# ZB2.net
KiCad netlist of a schematic drawn in Altium Designer
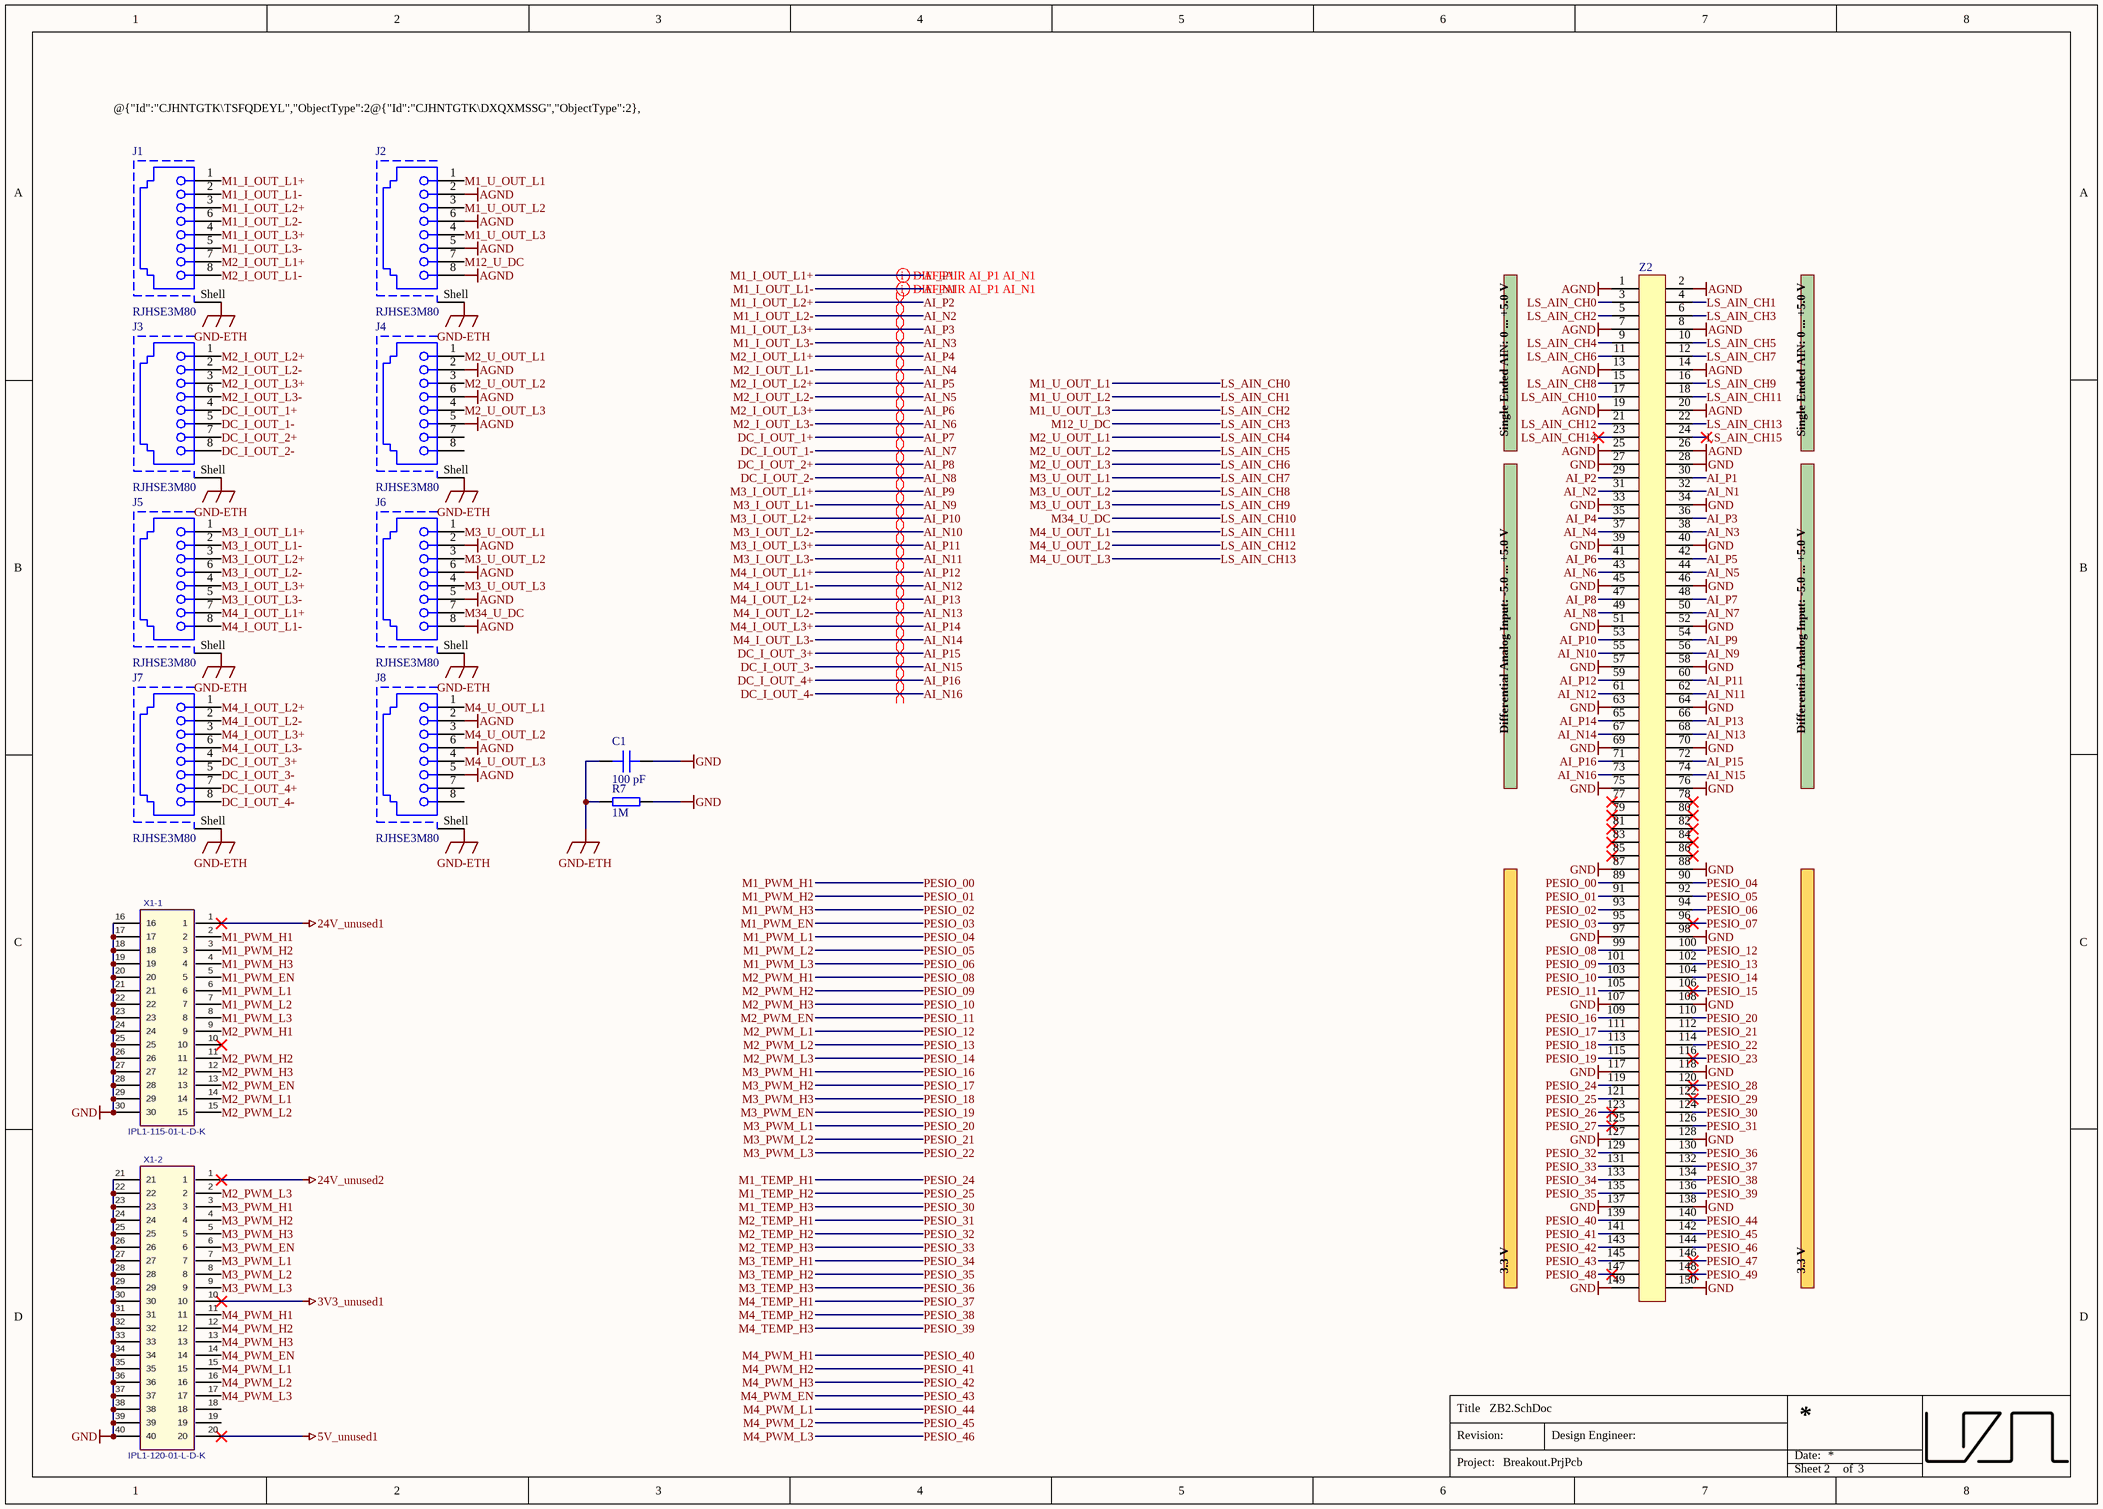
[diagram p0: ZB2.SchDoc]

(export (version "E")
  (design (tool "Eeschema 10.0.6"))
  (components
    (comp (ref "C1")
      (value "100 pF")
      (footprint "C_1206_TE")
      (description "2kV 100pF NP0 ±5% 1206 Multilayer Ceramic Capacitors MLCC - SMD/SMT ROHS")
      (fields
        (field (name "MANUFACTURER PART NUMBER") "CC1206JKNPODBN101")
        (field (name "MANUFACTURER") "YAGEO")
        (field (name "CREATED FROM") "AGeiger")
      )
      (libsource (lib "user") (part "Capacitor"))
    )
    (comp (ref "J1")
      (value "RJHSE3M80")
      (footprint "RJHSE3M80")
      (description "CAT5, RJ45 Connector, 1 port, vertical")
      (fields
        (field (name "MANUFACTURER") "Amphenol")
        (field (name "LCSC PART NUMBER") "C3179193")
        (field (name "CREATED FROM") "DHufnagel")
      )
      (libsource (lib "user") (part "RJHSE3M80"))
    )
    (comp (ref "J2")
      (value "RJHSE3M80")
      (footprint "RJHSE3M80")
      (description "CAT5, RJ45 Connector, 1 port, vertical")
      (fields
        (field (name "MANUFACTURER") "Amphenol")
        (field (name "LCSC PART NUMBER") "C3179193")
        (field (name "CREATED FROM") "DHufnagel")
      )
      (libsource (lib "user") (part "RJHSE3M80"))
    )
    (comp (ref "J3")
      (value "RJHSE3M80")
      (footprint "RJHSE3M80")
      (description "CAT5, RJ45 Connector, 1 port, vertical")
      (fields
        (field (name "MANUFACTURER") "Amphenol")
        (field (name "LCSC PART NUMBER") "C3179193")
        (field (name "CREATED FROM") "DHufnagel")
      )
      (libsource (lib "user") (part "RJHSE3M80"))
    )
    (comp (ref "J4")
      (value "RJHSE3M80")
      (footprint "RJHSE3M80")
      (description "CAT5, RJ45 Connector, 1 port, vertical")
      (fields
        (field (name "MANUFACTURER") "Amphenol")
        (field (name "LCSC PART NUMBER") "C3179193")
        (field (name "CREATED FROM") "DHufnagel")
      )
      (libsource (lib "user") (part "RJHSE3M80"))
    )
    (comp (ref "J5")
      (value "RJHSE3M80")
      (footprint "RJHSE3M80")
      (description "CAT5, RJ45 Connector, 1 port, vertical")
      (fields
        (field (name "MANUFACTURER") "Amphenol")
        (field (name "LCSC PART NUMBER") "C3179193")
        (field (name "CREATED FROM") "DHufnagel")
      )
      (libsource (lib "user") (part "RJHSE3M80"))
    )
    (comp (ref "J6")
      (value "RJHSE3M80")
      (footprint "RJHSE3M80")
      (description "CAT5, RJ45 Connector, 1 port, vertical")
      (fields
        (field (name "MANUFACTURER") "Amphenol")
        (field (name "LCSC PART NUMBER") "C3179193")
        (field (name "CREATED FROM") "DHufnagel")
      )
      (libsource (lib "user") (part "RJHSE3M80"))
    )
    (comp (ref "J7")
      (value "RJHSE3M80")
      (footprint "RJHSE3M80")
      (description "CAT5, RJ45 Connector, 1 port, vertical")
      (fields
        (field (name "MANUFACTURER") "Amphenol")
        (field (name "LCSC PART NUMBER") "C3179193")
        (field (name "CREATED FROM") "DHufnagel")
      )
      (libsource (lib "user") (part "RJHSE3M80"))
    )
    (comp (ref "J8")
      (value "RJHSE3M80")
      (footprint "RJHSE3M80")
      (description "CAT5, RJ45 Connector, 1 port, vertical")
      (fields
        (field (name "MANUFACTURER") "Amphenol")
        (field (name "LCSC PART NUMBER") "C3179193")
        (field (name "CREATED FROM") "DHufnagel")
      )
      (libsource (lib "user") (part "RJHSE3M80"))
    )
    (comp (ref "R7")
      (value "1M")
      (footprint "RES 1206_3216")
      (fields
        (field (name "MANUFACTURER PART NUMBER") "1206W4F1004T5E")
        (field (name "MANUFACTURER") "UNI-ROYAL")
        (field (name "TOLERANCE") "1%")
        (field (name "CREATED FROM") "AGeiger")
      )
      (libsource (lib "user") (part "Resistor"))
    )
    (comp (ref "X1-1")
      (value "IPL1-115-01-L-D-K")
      (footprint "IPL1-115-01-YYY-D-K")
      (description "2.54 mm Double Row Terminal Assembly")
      (fields (field (name "MANUFACTURER") "SAMTEC") (field (name "CREATED FROM") "MGremer"))
      (libsource (lib "user") (part "IPL1-115-01-XX-D-XX"))
    )
    (comp (ref "X1-2")
      (value "IPL1-120-01-L-D-K")
      (footprint "SAMTEC_IPL1-120-01-X-D-K")
      (description "Terminal Assembly, Double Row, Thru-Hole, 2.54 mm x 2.54 mm Pitch, 40 Pins")
      (fields (field (name "MANUFACTURER") "SAMTEC") (field (name "CREATED FROM") "PBaumann"))
      (libsource (lib "user") (part "IPL1-120-01-XX-D-XX"))
    )
    (comp (ref "Z2")
      (value "~")
      (footprint "ERM8-075-02.0-L-DV")
      (description "0.80 mm Edge Rate Rugged High Speed")
      (fields
        (field (name "MANUFACTURER PART NUMBER") "ERM8-075-02.0-L-DV-TR")
        (field (name "MANUFACTURER") "SAMTEC")
        (field (name "CREATED FROM") "AGeiger")
      )
      (libsource (lib "user") (part "CON-150"))
    )
  )
  (nets
    (net (code "1") (name "/AI_N1") (class "Default")
      (node (ref "J1") (pin "2") (pinfunction "2_2") (pintype "passive"))
      (node (ref "Z2") (pin "32") (pinfunction "32_32") (pintype "passive"))
    )
    (net (code "2") (name "/AI_N2") (class "Default")
      (node (ref "J1") (pin "6") (pinfunction "6_6") (pintype "passive"))
      (node (ref "Z2") (pin "31") (pinfunction "31_31") (pintype "passive"))
    )
    (net (code "3") (name "/AI_N3") (class "Default")
      (node (ref "J1") (pin "5") (pinfunction "5_5") (pintype "passive"))
      (node (ref "Z2") (pin "38") (pinfunction "38_38") (pintype "passive"))
    )
    (net (code "4") (name "/AI_N4") (class "Default")
      (node (ref "J1") (pin "8") (pinfunction "8_8") (pintype "passive"))
      (node (ref "Z2") (pin "37") (pinfunction "37_37") (pintype "passive"))
    )
    (net (code "5") (name "/AI_N5") (class "Default")
      (node (ref "J3") (pin "2") (pinfunction "2_2") (pintype "passive"))
      (node (ref "Z2") (pin "44") (pinfunction "44_44") (pintype "passive"))
    )
    (net (code "6") (name "/AI_N6") (class "Default")
      (node (ref "J3") (pin "6") (pinfunction "6_6") (pintype "passive"))
      (node (ref "Z2") (pin "43") (pinfunction "43_43") (pintype "passive"))
    )
    (net (code "7") (name "/AI_N7") (class "Default")
      (node (ref "J3") (pin "5") (pinfunction "5_5") (pintype "passive"))
      (node (ref "Z2") (pin "50") (pinfunction "50_50") (pintype "passive"))
    )
    (net (code "8") (name "/AI_N8") (class "Default")
      (node (ref "J3") (pin "8") (pinfunction "8_8") (pintype "passive"))
      (node (ref "Z2") (pin "49") (pinfunction "49_49") (pintype "passive"))
    )
    (net (code "9") (name "/AI_N9") (class "Default")
      (node (ref "J5") (pin "2") (pinfunction "2_2") (pintype "passive"))
      (node (ref "Z2") (pin "56") (pinfunction "56_56") (pintype "passive"))
    )
    (net (code "10") (name "/AI_N10") (class "Default")
      (node (ref "J5") (pin "6") (pinfunction "6_6") (pintype "passive"))
      (node (ref "Z2") (pin "55") (pinfunction "55_55") (pintype "passive"))
    )
    (net (code "11") (name "/AI_N11") (class "Default")
      (node (ref "J5") (pin "5") (pinfunction "5_5") (pintype "passive"))
      (node (ref "Z2") (pin "62") (pinfunction "62_62") (pintype "passive"))
    )
    (net (code "12") (name "/AI_N12") (class "Default")
      (node (ref "J5") (pin "8") (pinfunction "8_8") (pintype "passive"))
      (node (ref "Z2") (pin "61") (pinfunction "61_61") (pintype "passive"))
    )
    (net (code "13") (name "/AI_N13") (class "Default")
      (node (ref "J7") (pin "2") (pinfunction "2_2") (pintype "passive"))
      (node (ref "Z2") (pin "68") (pinfunction "68_68") (pintype "passive"))
    )
    (net (code "14") (name "/AI_N14") (class "Default")
      (node (ref "J7") (pin "6") (pinfunction "6_6") (pintype "passive"))
      (node (ref "Z2") (pin "67") (pinfunction "67_67") (pintype "passive"))
    )
    (net (code "15") (name "/AI_N15") (class "Default")
      (node (ref "J7") (pin "5") (pinfunction "5_5") (pintype "passive"))
      (node (ref "Z2") (pin "74") (pinfunction "74_74") (pintype "passive"))
    )
    (net (code "16") (name "/AI_N16") (class "Default")
      (node (ref "J7") (pin "8") (pinfunction "8_8") (pintype "passive"))
      (node (ref "Z2") (pin "73") (pinfunction "73_73") (pintype "passive"))
    )
    (net (code "17") (name "/AI_P1") (class "Default")
      (node (ref "J1") (pin "1") (pinfunction "1_1") (pintype "passive"))
      (node (ref "Z2") (pin "30") (pinfunction "30_30") (pintype "passive"))
    )
    (net (code "18") (name "/AI_P2") (class "Default")
      (node (ref "J1") (pin "3") (pinfunction "3_3") (pintype "passive"))
      (node (ref "Z2") (pin "29") (pinfunction "29_29") (pintype "passive"))
    )
    (net (code "19") (name "/AI_P3") (class "Default")
      (node (ref "J1") (pin "4") (pinfunction "4_4") (pintype "passive"))
      (node (ref "Z2") (pin "36") (pinfunction "36_36") (pintype "passive"))
    )
    (net (code "20") (name "/AI_P4") (class "Default")
      (node (ref "J1") (pin "7") (pinfunction "7_7") (pintype "passive"))
      (node (ref "Z2") (pin "35") (pinfunction "35_35") (pintype "passive"))
    )
    (net (code "21") (name "/AI_P5") (class "Default")
      (node (ref "J3") (pin "1") (pinfunction "1_1") (pintype "passive"))
      (node (ref "Z2") (pin "42") (pinfunction "42_42") (pintype "passive"))
    )
    (net (code "22") (name "/AI_P6") (class "Default")
      (node (ref "J3") (pin "3") (pinfunction "3_3") (pintype "passive"))
      (node (ref "Z2") (pin "41") (pinfunction "41_41") (pintype "passive"))
    )
    (net (code "23") (name "/AI_P7") (class "Default")
      (node (ref "J3") (pin "4") (pinfunction "4_4") (pintype "passive"))
      (node (ref "Z2") (pin "48") (pinfunction "48_48") (pintype "passive"))
    )
    (net (code "24") (name "/AI_P8") (class "Default")
      (node (ref "J3") (pin "7") (pinfunction "7_7") (pintype "passive"))
      (node (ref "Z2") (pin "47") (pinfunction "47_47") (pintype "passive"))
    )
    (net (code "25") (name "/AI_P9") (class "Default")
      (node (ref "J5") (pin "1") (pinfunction "1_1") (pintype "passive"))
      (node (ref "Z2") (pin "54") (pinfunction "54_54") (pintype "passive"))
    )
    (net (code "26") (name "/AI_P10") (class "Default")
      (node (ref "J5") (pin "3") (pinfunction "3_3") (pintype "passive"))
      (node (ref "Z2") (pin "53") (pinfunction "53_53") (pintype "passive"))
    )
    (net (code "27") (name "/AI_P11") (class "Default")
      (node (ref "J5") (pin "4") (pinfunction "4_4") (pintype "passive"))
      (node (ref "Z2") (pin "60") (pinfunction "60_60") (pintype "passive"))
    )
    (net (code "28") (name "/AI_P12") (class "Default")
      (node (ref "J5") (pin "7") (pinfunction "7_7") (pintype "passive"))
      (node (ref "Z2") (pin "59") (pinfunction "59_59") (pintype "passive"))
    )
    (net (code "29") (name "/AI_P13") (class "Default")
      (node (ref "J7") (pin "1") (pinfunction "1_1") (pintype "passive"))
      (node (ref "Z2") (pin "66") (pinfunction "66_66") (pintype "passive"))
    )
    (net (code "30") (name "/AI_P14") (class "Default")
      (node (ref "J7") (pin "3") (pinfunction "3_3") (pintype "passive"))
      (node (ref "Z2") (pin "65") (pinfunction "65_65") (pintype "passive"))
    )
    (net (code "31") (name "/AI_P15") (class "Default")
      (node (ref "J7") (pin "4") (pinfunction "4_4") (pintype "passive"))
      (node (ref "Z2") (pin "72") (pinfunction "72_72") (pintype "passive"))
    )
    (net (code "32") (name "/AI_P16") (class "Default")
      (node (ref "J7") (pin "7") (pinfunction "7_7") (pintype "passive"))
      (node (ref "Z2") (pin "71") (pinfunction "71_71") (pintype "passive"))
    )
    (net (code "33") (name "/LS_AIN_CH0") (class "Default")
      (node (ref "J2") (pin "1") (pinfunction "1_1") (pintype "passive"))
      (node (ref "Z2") (pin "3") (pinfunction "3_3") (pintype "passive"))
    )
    (net (code "34") (name "/LS_AIN_CH1") (class "Default")
      (node (ref "J2") (pin "3") (pinfunction "3_3") (pintype "passive"))
      (node (ref "Z2") (pin "4") (pinfunction "4_4") (pintype "passive"))
    )
    (net (code "35") (name "/LS_AIN_CH2") (class "Default")
      (node (ref "J2") (pin "4") (pinfunction "4_4") (pintype "passive"))
      (node (ref "Z2") (pin "5") (pinfunction "5_5") (pintype "passive"))
    )
    (net (code "36") (name "/LS_AIN_CH3") (class "Default")
      (node (ref "J2") (pin "7") (pinfunction "7_7") (pintype "passive"))
      (node (ref "Z2") (pin "6") (pinfunction "6_6") (pintype "passive"))
    )
    (net (code "37") (name "/LS_AIN_CH4") (class "Default")
      (node (ref "J4") (pin "1") (pinfunction "1_1") (pintype "passive"))
      (node (ref "Z2") (pin "9") (pinfunction "9_9") (pintype "passive"))
    )
    (net (code "38") (name "/LS_AIN_CH5") (class "Default")
      (node (ref "J4") (pin "3") (pinfunction "3_3") (pintype "passive"))
      (node (ref "Z2") (pin "10") (pinfunction "10_10") (pintype "passive"))
    )
    (net (code "39") (name "/LS_AIN_CH6") (class "Default")
      (node (ref "J4") (pin "4") (pinfunction "4_4") (pintype "passive"))
      (node (ref "Z2") (pin "11") (pinfunction "11_11") (pintype "passive"))
    )
    (net (code "40") (name "/LS_AIN_CH7") (class "Default")
      (node (ref "J6") (pin "1") (pinfunction "1_1") (pintype "passive"))
      (node (ref "Z2") (pin "12") (pinfunction "12_12") (pintype "passive"))
    )
    (net (code "41") (name "/LS_AIN_CH8") (class "Default")
      (node (ref "J6") (pin "3") (pinfunction "3_3") (pintype "passive"))
      (node (ref "Z2") (pin "15") (pinfunction "15_15") (pintype "passive"))
    )
    (net (code "42") (name "/LS_AIN_CH9") (class "Default")
      (node (ref "J6") (pin "4") (pinfunction "4_4") (pintype "passive"))
      (node (ref "Z2") (pin "16") (pinfunction "16_16") (pintype "passive"))
    )
    (net (code "43") (name "/LS_AIN_CH10") (class "Default")
      (node (ref "J6") (pin "7") (pinfunction "7_7") (pintype "passive"))
      (node (ref "Z2") (pin "17") (pinfunction "17_17") (pintype "passive"))
    )
    (net (code "44") (name "/LS_AIN_CH11") (class "Default")
      (node (ref "J8") (pin "1") (pinfunction "1_1") (pintype "passive"))
      (node (ref "Z2") (pin "18") (pinfunction "18_18") (pintype "passive"))
    )
    (net (code "45") (name "/LS_AIN_CH12") (class "Default")
      (node (ref "J8") (pin "3") (pinfunction "3_3") (pintype "passive"))
      (node (ref "Z2") (pin "21") (pinfunction "21_21") (pintype "passive"))
    )
    (net (code "46") (name "/LS_AIN_CH13") (class "Default")
      (node (ref "J8") (pin "4") (pinfunction "4_4") (pintype "passive"))
      (node (ref "Z2") (pin "22") (pinfunction "22_22") (pintype "passive"))
    )
    (net (code "47") (name "/LS_AIN_CH14") (class "Default")
      (node (ref "Z2") (pin "23") (pinfunction "23_23") (pintype "passive+no_connect"))
    )
    (net (code "48") (name "/LS_AIN_CH15") (class "Default")
      (node (ref "Z2") (pin "24") (pinfunction "24_24") (pintype "passive+no_connect"))
    )
    (net (code "49") (name "/M1_PWM_EN") (class "Default")
      (node (ref "X1-1") (pin "5") (pinfunction "5_5") (pintype "passive"))
      (node (ref "Z2") (pin "95") (pinfunction "95_95") (pintype "passive"))
    )
    (net (code "50") (name "/M1_PWM_H1") (class "Default")
      (node (ref "X1-1") (pin "2") (pinfunction "2_2") (pintype "passive"))
      (node (ref "Z2") (pin "89") (pinfunction "89_89") (pintype "passive"))
    )
    (net (code "51") (name "/M1_PWM_H2") (class "Default")
      (node (ref "X1-1") (pin "3") (pinfunction "3_3") (pintype "passive"))
      (node (ref "Z2") (pin "91") (pinfunction "91_91") (pintype "passive"))
    )
    (net (code "52") (name "/M1_PWM_H3") (class "Default")
      (node (ref "X1-1") (pin "4") (pinfunction "4_4") (pintype "passive"))
      (node (ref "Z2") (pin "93") (pinfunction "93_93") (pintype "passive"))
    )
    (net (code "53") (name "/M1_PWM_L1") (class "Default")
      (node (ref "X1-1") (pin "6") (pinfunction "6_6") (pintype "passive"))
      (node (ref "Z2") (pin "90") (pinfunction "90_90") (pintype "passive"))
    )
    (net (code "54") (name "/M1_PWM_L2") (class "Default")
      (node (ref "X1-1") (pin "7") (pinfunction "7_7") (pintype "passive"))
      (node (ref "Z2") (pin "92") (pinfunction "92_92") (pintype "passive"))
    )
    (net (code "55") (name "/M1_PWM_L3") (class "Default")
      (node (ref "X1-1") (pin "8") (pinfunction "8_8") (pintype "passive"))
      (node (ref "Z2") (pin "94") (pinfunction "94_94") (pintype "passive"))
    )
    (net (code "56") (name "/M1_TEMP_H1") (class "Default")
      (node (ref "Z2") (pin "119") (pinfunction "119_119") (pintype "passive"))
    )
    (net (code "57") (name "/M1_TEMP_H2") (class "Default")
      (node (ref "Z2") (pin "121") (pinfunction "121_121") (pintype "passive"))
    )
    (net (code "58") (name "/M1_TEMP_H3") (class "Default")
      (node (ref "Z2") (pin "124") (pinfunction "124_124") (pintype "passive"))
    )
    (net (code "59") (name "/M2_PWM_EN") (class "Default")
      (node (ref "X1-1") (pin "13") (pinfunction "13_13") (pintype "passive"))
      (node (ref "Z2") (pin "105") (pinfunction "105_105") (pintype "passive"))
    )
    (net (code "60") (name "/M2_PWM_H1") (class "Default")
      (node (ref "X1-1") (pin "9") (pinfunction "9_9") (pintype "passive"))
      (node (ref "Z2") (pin "99") (pinfunction "99_99") (pintype "passive"))
    )
    (net (code "61") (name "/M2_PWM_H2") (class "Default")
      (node (ref "X1-1") (pin "11") (pinfunction "11_11") (pintype "passive"))
      (node (ref "Z2") (pin "101") (pinfunction "101_101") (pintype "passive"))
    )
    (net (code "62") (name "/M2_PWM_H3") (class "Default")
      (node (ref "X1-1") (pin "12") (pinfunction "12_12") (pintype "passive"))
      (node (ref "Z2") (pin "103") (pinfunction "103_103") (pintype "passive"))
    )
    (net (code "63") (name "/M2_PWM_L1") (class "Default")
      (node (ref "X1-1") (pin "14") (pinfunction "14_14") (pintype "passive"))
      (node (ref "Z2") (pin "100") (pinfunction "100_100") (pintype "passive"))
    )
    (net (code "64") (name "/M2_PWM_L2") (class "Default")
      (node (ref "X1-1") (pin "15") (pinfunction "15_15") (pintype "passive"))
      (node (ref "Z2") (pin "102") (pinfunction "102_102") (pintype "passive"))
    )
    (net (code "65") (name "/M2_PWM_L3") (class "Default")
      (node (ref "X1-2") (pin "2") (pinfunction "2_2") (pintype "passive"))
      (node (ref "Z2") (pin "104") (pinfunction "104_104") (pintype "passive"))
    )
    (net (code "66") (name "/M2_TEMP_H1") (class "Default")
      (node (ref "Z2") (pin "126") (pinfunction "126_126") (pintype "passive"))
    )
    (net (code "67") (name "/M2_TEMP_H2") (class "Default")
      (node (ref "Z2") (pin "129") (pinfunction "129_129") (pintype "passive"))
    )
    (net (code "68") (name "/M2_TEMP_H3") (class "Default")
      (node (ref "Z2") (pin "131") (pinfunction "131_131") (pintype "passive"))
    )
    (net (code "69") (name "/M3_PWM_EN") (class "Default")
      (node (ref "X1-2") (pin "6") (pinfunction "6_6") (pintype "passive"))
      (node (ref "Z2") (pin "115") (pinfunction "115_115") (pintype "passive"))
    )
    (net (code "70") (name "/M3_PWM_H1") (class "Default")
      (node (ref "X1-2") (pin "3") (pinfunction "3_3") (pintype "passive"))
      (node (ref "Z2") (pin "109") (pinfunction "109_109") (pintype "passive"))
    )
    (net (code "71") (name "/M3_PWM_H2") (class "Default")
      (node (ref "X1-2") (pin "4") (pinfunction "4_4") (pintype "passive"))
      (node (ref "Z2") (pin "111") (pinfunction "111_111") (pintype "passive"))
    )
    (net (code "72") (name "/M3_PWM_H3") (class "Default")
      (node (ref "X1-2") (pin "5") (pinfunction "5_5") (pintype "passive"))
      (node (ref "Z2") (pin "113") (pinfunction "113_113") (pintype "passive"))
    )
    (net (code "73") (name "/M3_PWM_L1") (class "Default")
      (node (ref "X1-2") (pin "7") (pinfunction "7_7") (pintype "passive"))
      (node (ref "Z2") (pin "110") (pinfunction "110_110") (pintype "passive"))
    )
    (net (code "74") (name "/M3_PWM_L2") (class "Default")
      (node (ref "X1-2") (pin "8") (pinfunction "8_8") (pintype "passive"))
      (node (ref "Z2") (pin "112") (pinfunction "112_112") (pintype "passive"))
    )
    (net (code "75") (name "/M3_PWM_L3") (class "Default")
      (node (ref "X1-2") (pin "9") (pinfunction "9_9") (pintype "passive"))
      (node (ref "Z2") (pin "114") (pinfunction "114_114") (pintype "passive"))
    )
    (net (code "76") (name "/M3_TEMP_H1") (class "Default")
      (node (ref "Z2") (pin "133") (pinfunction "133_133") (pintype "passive"))
    )
    (net (code "77") (name "/M3_TEMP_H2") (class "Default")
      (node (ref "Z2") (pin "135") (pinfunction "135_135") (pintype "passive"))
    )
    (net (code "78") (name "/M3_TEMP_H3") (class "Default")
      (node (ref "Z2") (pin "130") (pinfunction "130_130") (pintype "passive"))
    )
    (net (code "79") (name "/M4_PWM_EN") (class "Default")
      (node (ref "X1-2") (pin "14") (pinfunction "14_14") (pintype "passive"))
      (node (ref "Z2") (pin "145") (pinfunction "145_145") (pintype "passive"))
    )
    (net (code "80") (name "/M4_PWM_H1") (class "Default")
      (node (ref "X1-2") (pin "11") (pinfunction "11_11") (pintype "passive"))
      (node (ref "Z2") (pin "139") (pinfunction "139_139") (pintype "passive"))
    )
    (net (code "81") (name "/M4_PWM_H2") (class "Default")
      (node (ref "X1-2") (pin "12") (pinfunction "12_12") (pintype "passive"))
      (node (ref "Z2") (pin "141") (pinfunction "141_141") (pintype "passive"))
    )
    (net (code "82") (name "/M4_PWM_H3") (class "Default")
      (node (ref "X1-2") (pin "13") (pinfunction "13_13") (pintype "passive"))
      (node (ref "Z2") (pin "143") (pinfunction "143_143") (pintype "passive"))
    )
    (net (code "83") (name "/M4_PWM_L1") (class "Default")
      (node (ref "X1-2") (pin "15") (pinfunction "15_15") (pintype "passive"))
      (node (ref "Z2") (pin "140") (pinfunction "140_140") (pintype "passive"))
    )
    (net (code "84") (name "/M4_PWM_L2") (class "Default")
      (node (ref "X1-2") (pin "16") (pinfunction "16_16") (pintype "passive"))
      (node (ref "Z2") (pin "142") (pinfunction "142_142") (pintype "passive"))
    )
    (net (code "85") (name "/M4_PWM_L3") (class "Default")
      (node (ref "X1-2") (pin "17") (pinfunction "17_17") (pintype "passive"))
      (node (ref "Z2") (pin "144") (pinfunction "144_144") (pintype "passive"))
    )
    (net (code "86") (name "/M4_TEMP_H1") (class "Default")
      (node (ref "Z2") (pin "132") (pinfunction "132_132") (pintype "passive"))
    )
    (net (code "87") (name "/M4_TEMP_H2") (class "Default")
      (node (ref "Z2") (pin "134") (pinfunction "134_134") (pintype "passive"))
    )
    (net (code "88") (name "/M4_TEMP_H3") (class "Default")
      (node (ref "Z2") (pin "136") (pinfunction "136_136") (pintype "passive"))
    )
    (net (code "89") (name "/PESIO_07") (class "Default")
      (node (ref "Z2") (pin "96") (pinfunction "96_96") (pintype "passive+no_connect"))
    )
    (net (code "90") (name "/PESIO_15") (class "Default")
      (node (ref "Z2") (pin "106") (pinfunction "106_106") (pintype "passive+no_connect"))
    )
    (net (code "91") (name "/PESIO_23") (class "Default")
      (node (ref "Z2") (pin "116") (pinfunction "116_116") (pintype "passive+no_connect"))
    )
    (net (code "92") (name "/PESIO_26") (class "Default")
      (node (ref "Z2") (pin "123") (pinfunction "123_123") (pintype "passive+no_connect"))
    )
    (net (code "93") (name "/PESIO_27") (class "Default")
      (node (ref "Z2") (pin "125") (pinfunction "125_125") (pintype "passive+no_connect"))
    )
    (net (code "94") (name "/PESIO_28") (class "Default")
      (node (ref "Z2") (pin "120") (pinfunction "120_120") (pintype "passive+no_connect"))
    )
    (net (code "95") (name "/PESIO_29") (class "Default")
      (node (ref "Z2") (pin "122") (pinfunction "122_122") (pintype "passive+no_connect"))
    )
    (net (code "96") (name "/PESIO_47") (class "Default")
      (node (ref "Z2") (pin "146") (pinfunction "146_146") (pintype "passive+no_connect"))
    )
    (net (code "97") (name "/PESIO_48") (class "Default")
      (node (ref "Z2") (pin "147") (pinfunction "147_147") (pintype "passive+no_connect"))
    )
    (net (code "98") (name "/PESIO_49") (class "Default")
      (node (ref "Z2") (pin "148") (pinfunction "148_148") (pintype "passive+no_connect"))
    )
    (net (code "99") (name "3V3_unused1") (class "Default")
      (node (ref "X1-2") (pin "10") (pinfunction "10_10") (pintype "passive"))
    )
    (net (code "100") (name "5V_unused1") (class "Default")
      (node (ref "X1-2") (pin "20") (pinfunction "20_20") (pintype "passive"))
    )
    (net (code "101") (name "24V_unused1") (class "Default")
      (node (ref "X1-1") (pin "1") (pinfunction "1_1") (pintype "passive"))
    )
    (net (code "102") (name "24V_unused2") (class "Default")
      (node (ref "X1-2") (pin "1") (pinfunction "1_1") (pintype "passive"))
    )
    (net (code "103") (name "AGND") (class "Default")
      (node (ref "J2") (pin "2") (pinfunction "2_2") (pintype "passive"))
      (node (ref "J2") (pin "5") (pinfunction "5_5") (pintype "passive"))
      (node (ref "J2") (pin "6") (pinfunction "6_6") (pintype "passive"))
      (node (ref "J2") (pin "8") (pinfunction "8_8") (pintype "passive"))
      (node (ref "J4") (pin "2") (pinfunction "2_2") (pintype "passive"))
      (node (ref "J4") (pin "5") (pinfunction "5_5") (pintype "passive"))
      (node (ref "J4") (pin "6") (pinfunction "6_6") (pintype "passive"))
      (node (ref "J6") (pin "2") (pinfunction "2_2") (pintype "passive"))
      (node (ref "J6") (pin "5") (pinfunction "5_5") (pintype "passive"))
      (node (ref "J6") (pin "6") (pinfunction "6_6") (pintype "passive"))
      (node (ref "J6") (pin "8") (pinfunction "8_8") (pintype "passive"))
      (node (ref "J8") (pin "2") (pinfunction "2_2") (pintype "passive"))
      (node (ref "J8") (pin "5") (pinfunction "5_5") (pintype "passive"))
      (node (ref "J8") (pin "6") (pinfunction "6_6") (pintype "passive"))
      (node (ref "Z2") (pin "1") (pinfunction "1_1") (pintype "passive"))
      (node (ref "Z2") (pin "13") (pinfunction "13_13") (pintype "passive"))
      (node (ref "Z2") (pin "14") (pinfunction "14_14") (pintype "passive"))
      (node (ref "Z2") (pin "19") (pinfunction "19_19") (pintype "passive"))
      (node (ref "Z2") (pin "2") (pinfunction "2_2") (pintype "passive"))
      (node (ref "Z2") (pin "20") (pinfunction "20_20") (pintype "passive"))
      (node (ref "Z2") (pin "25") (pinfunction "25_25") (pintype "passive"))
      (node (ref "Z2") (pin "26") (pinfunction "26_26") (pintype "passive"))
      (node (ref "Z2") (pin "7") (pinfunction "7_7") (pintype "passive"))
      (node (ref "Z2") (pin "8") (pinfunction "8_8") (pintype "passive"))
    )
    (net (code "104") (name "GND") (class "Default")
      (node (ref "C1") (pin "2") (pinfunction "2_2") (pintype "passive"))
      (node (ref "R7") (pin "2") (pinfunction "2_2") (pintype "passive"))
      (node (ref "X1-1") (pin "16") (pinfunction "16_16") (pintype "passive"))
      (node (ref "X1-1") (pin "17") (pinfunction "17_17") (pintype "passive"))
      (node (ref "X1-1") (pin "18") (pinfunction "18_18") (pintype "passive"))
      (node (ref "X1-1") (pin "19") (pinfunction "19_19") (pintype "passive"))
      (node (ref "X1-1") (pin "20") (pinfunction "20_20") (pintype "passive"))
      (node (ref "X1-1") (pin "21") (pinfunction "21_21") (pintype "passive"))
      (node (ref "X1-1") (pin "22") (pinfunction "22_22") (pintype "passive"))
      (node (ref "X1-1") (pin "23") (pinfunction "23_23") (pintype "passive"))
      (node (ref "X1-1") (pin "24") (pinfunction "24_24") (pintype "passive"))
      (node (ref "X1-1") (pin "25") (pinfunction "25_25") (pintype "passive"))
      (node (ref "X1-1") (pin "26") (pinfunction "26_26") (pintype "passive"))
      (node (ref "X1-1") (pin "27") (pinfunction "27_27") (pintype "passive"))
      (node (ref "X1-1") (pin "28") (pinfunction "28_28") (pintype "passive"))
      (node (ref "X1-1") (pin "29") (pinfunction "29_29") (pintype "passive"))
      (node (ref "X1-1") (pin "30") (pinfunction "30_30") (pintype "passive"))
      (node (ref "X1-2") (pin "21") (pinfunction "21_21") (pintype "passive"))
      (node (ref "X1-2") (pin "22") (pinfunction "22_22") (pintype "passive"))
      (node (ref "X1-2") (pin "23") (pinfunction "23_23") (pintype "passive"))
      (node (ref "X1-2") (pin "24") (pinfunction "24_24") (pintype "passive"))
      (node (ref "X1-2") (pin "25") (pinfunction "25_25") (pintype "passive"))
      (node (ref "X1-2") (pin "26") (pinfunction "26_26") (pintype "passive"))
      (node (ref "X1-2") (pin "27") (pinfunction "27_27") (pintype "passive"))
      (node (ref "X1-2") (pin "28") (pinfunction "28_28") (pintype "passive"))
      (node (ref "X1-2") (pin "29") (pinfunction "29_29") (pintype "passive"))
      (node (ref "X1-2") (pin "30") (pinfunction "30_30") (pintype "passive"))
      (node (ref "X1-2") (pin "31") (pinfunction "31_31") (pintype "passive"))
      (node (ref "X1-2") (pin "32") (pinfunction "32_32") (pintype "passive"))
      (node (ref "X1-2") (pin "33") (pinfunction "33_33") (pintype "passive"))
      (node (ref "X1-2") (pin "34") (pinfunction "34_34") (pintype "passive"))
      (node (ref "X1-2") (pin "35") (pinfunction "35_35") (pintype "passive"))
      (node (ref "X1-2") (pin "36") (pinfunction "36_36") (pintype "passive"))
      (node (ref "X1-2") (pin "37") (pinfunction "37_37") (pintype "passive"))
      (node (ref "X1-2") (pin "38") (pinfunction "38_38") (pintype "passive"))
      (node (ref "X1-2") (pin "39") (pinfunction "39_39") (pintype "passive"))
      (node (ref "X1-2") (pin "40") (pinfunction "40_40") (pintype "passive"))
      (node (ref "Z2") (pin "107") (pinfunction "107_107") (pintype "passive"))
      (node (ref "Z2") (pin "108") (pinfunction "108_108") (pintype "passive"))
      (node (ref "Z2") (pin "117") (pinfunction "117_117") (pintype "passive"))
      (node (ref "Z2") (pin "118") (pinfunction "118_118") (pintype "passive"))
      (node (ref "Z2") (pin "127") (pinfunction "127_127") (pintype "passive"))
      (node (ref "Z2") (pin "128") (pinfunction "128_128") (pintype "passive"))
      (node (ref "Z2") (pin "137") (pinfunction "137_137") (pintype "passive"))
      (node (ref "Z2") (pin "138") (pinfunction "138_138") (pintype "passive"))
      (node (ref "Z2") (pin "149") (pinfunction "149_149") (pintype "passive"))
      (node (ref "Z2") (pin "150") (pinfunction "150_150") (pintype "passive"))
      (node (ref "Z2") (pin "27") (pinfunction "27_27") (pintype "passive"))
      (node (ref "Z2") (pin "28") (pinfunction "28_28") (pintype "passive"))
      (node (ref "Z2") (pin "33") (pinfunction "33_33") (pintype "passive"))
      (node (ref "Z2") (pin "34") (pinfunction "34_34") (pintype "passive"))
      (node (ref "Z2") (pin "39") (pinfunction "39_39") (pintype "passive"))
      (node (ref "Z2") (pin "40") (pinfunction "40_40") (pintype "passive"))
      (node (ref "Z2") (pin "45") (pinfunction "45_45") (pintype "passive"))
      (node (ref "Z2") (pin "46") (pinfunction "46_46") (pintype "passive"))
      (node (ref "Z2") (pin "51") (pinfunction "51_51") (pintype "passive"))
      (node (ref "Z2") (pin "52") (pinfunction "52_52") (pintype "passive"))
      (node (ref "Z2") (pin "57") (pinfunction "57_57") (pintype "passive"))
      (node (ref "Z2") (pin "58") (pinfunction "58_58") (pintype "passive"))
      (node (ref "Z2") (pin "63") (pinfunction "63_63") (pintype "passive"))
      (node (ref "Z2") (pin "64") (pinfunction "64_64") (pintype "passive"))
      (node (ref "Z2") (pin "69") (pinfunction "69_69") (pintype "passive"))
      (node (ref "Z2") (pin "70") (pinfunction "70_70") (pintype "passive"))
      (node (ref "Z2") (pin "75") (pinfunction "75_75") (pintype "passive"))
      (node (ref "Z2") (pin "76") (pinfunction "76_76") (pintype "passive"))
      (node (ref "Z2") (pin "87") (pinfunction "87_87") (pintype "passive"))
      (node (ref "Z2") (pin "88") (pinfunction "88_88") (pintype "passive"))
      (node (ref "Z2") (pin "97") (pinfunction "97_97") (pintype "passive"))
      (node (ref "Z2") (pin "98") (pinfunction "98_98") (pintype "passive"))
    )
    (net (code "105") (name "GND-ETH") (class "Default")
      (node (ref "C1") (pin "1") (pinfunction "1_1") (pintype "passive"))
      (node (ref "J1") (pin "Shell") (pinfunction "Shell_Shell") (pintype "passive"))
      (node (ref "J2") (pin "Shell") (pinfunction "Shell_Shell") (pintype "passive"))
      (node (ref "J3") (pin "Shell") (pinfunction "Shell_Shell") (pintype "passive"))
      (node (ref "J4") (pin "Shell") (pinfunction "Shell_Shell") (pintype "passive"))
      (node (ref "J5") (pin "Shell") (pinfunction "Shell_Shell") (pintype "passive"))
      (node (ref "J6") (pin "Shell") (pinfunction "Shell_Shell") (pintype "passive"))
      (node (ref "J7") (pin "Shell") (pinfunction "Shell_Shell") (pintype "passive"))
      (node (ref "J8") (pin "Shell") (pinfunction "Shell_Shell") (pintype "passive"))
      (node (ref "R7") (pin "1") (pinfunction "1_1") (pintype "passive"))
    )
    (net (code "106") (name "unconnected-(J4-Pad7)") (class "Default")
      (node (ref "J4") (pin "7") (pinfunction "7_7") (pintype "passive"))
    )
    (net (code "107") (name "unconnected-(J4-Pad8)") (class "Default")
      (node (ref "J4") (pin "8") (pinfunction "8_8") (pintype "passive"))
    )
    (net (code "108") (name "unconnected-(J8-Pad7)") (class "Default")
      (node (ref "J8") (pin "7") (pinfunction "7_7") (pintype "passive"))
    )
    (net (code "109") (name "unconnected-(J8-Pad8)") (class "Default")
      (node (ref "J8") (pin "8") (pinfunction "8_8") (pintype "passive"))
    )
    (net (code "110") (name "unconnected-(X1-1-Pad10)") (class "Default")
      (node (ref "X1-1") (pin "10") (pinfunction "10_10") (pintype "passive+no_connect"))
    )
    (net (code "111") (name "unconnected-(X1-2-Pad18)") (class "Default")
      (node (ref "X1-2") (pin "18") (pinfunction "18_18") (pintype "passive"))
    )
    (net (code "112") (name "unconnected-(X1-2-Pad19)") (class "Default")
      (node (ref "X1-2") (pin "19") (pinfunction "19_19") (pintype "passive"))
    )
    (net (code "113") (name "unconnected-(Z2-Pad77)") (class "Default")
      (node (ref "Z2") (pin "77") (pinfunction "77_77") (pintype "passive+no_connect"))
    )
    (net (code "114") (name "unconnected-(Z2-Pad78)") (class "Default")
      (node (ref "Z2") (pin "78") (pinfunction "78_78") (pintype "passive+no_connect"))
    )
    (net (code "115") (name "unconnected-(Z2-Pad79)") (class "Default")
      (node (ref "Z2") (pin "79") (pinfunction "79_79") (pintype "passive+no_connect"))
    )
    (net (code "116") (name "unconnected-(Z2-Pad80)") (class "Default")
      (node (ref "Z2") (pin "80") (pinfunction "80_80") (pintype "passive+no_connect"))
    )
    (net (code "117") (name "unconnected-(Z2-Pad81)") (class "Default")
      (node (ref "Z2") (pin "81") (pinfunction "81_81") (pintype "passive+no_connect"))
    )
    (net (code "118") (name "unconnected-(Z2-Pad82)") (class "Default")
      (node (ref "Z2") (pin "82") (pinfunction "82_82") (pintype "passive+no_connect"))
    )
    (net (code "119") (name "unconnected-(Z2-Pad83)") (class "Default")
      (node (ref "Z2") (pin "83") (pinfunction "83_83") (pintype "passive+no_connect"))
    )
    (net (code "120") (name "unconnected-(Z2-Pad84)") (class "Default")
      (node (ref "Z2") (pin "84") (pinfunction "84_84") (pintype "passive+no_connect"))
    )
    (net (code "121") (name "unconnected-(Z2-Pad85)") (class "Default")
      (node (ref "Z2") (pin "85") (pinfunction "85_85") (pintype "passive+no_connect"))
    )
    (net (code "122") (name "unconnected-(Z2-Pad86)") (class "Default")
      (node (ref "Z2") (pin "86") (pinfunction "86_86") (pintype "passive+no_connect"))
    )
  )
)
